# MCU.net
KiCad netlist of a schematic drawn in Altium Designer
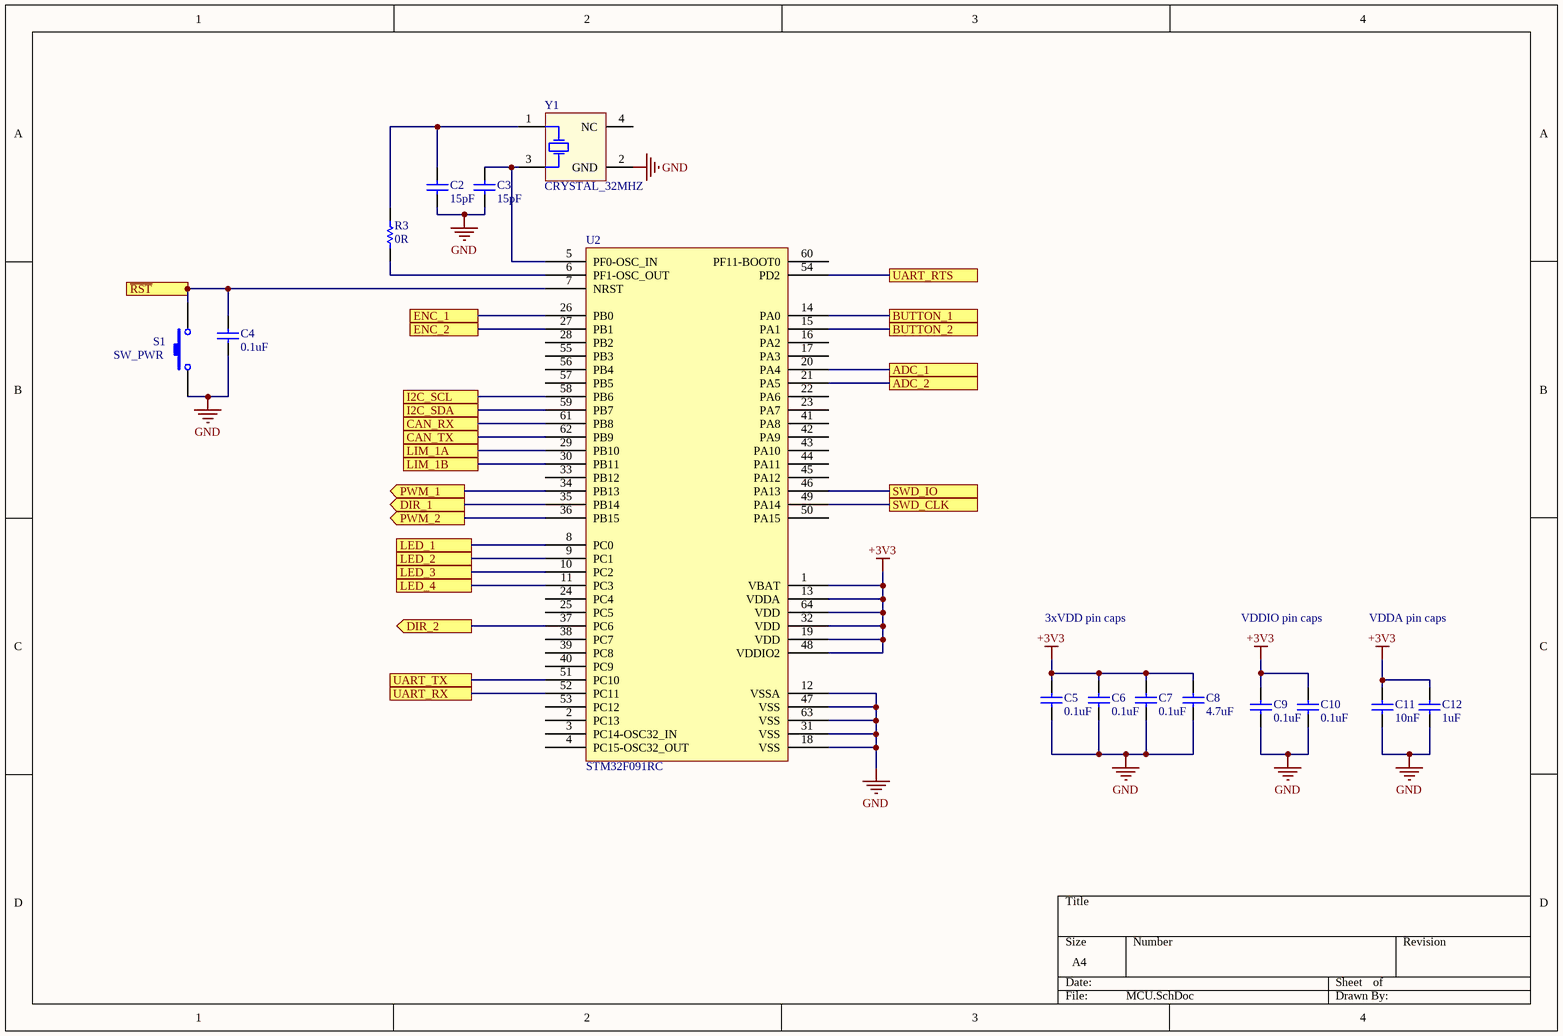
[diagram p0: MCU.SchDoc]

(export (version "E")
  (design (tool "Eeschema 10.0.6"))
  (components
    (comp (ref "C2")
      (value "15pF")
      (footprint "CAPC0603(1608)55_N")
      (description "CAP CER 15PF 250V NPO 0603")
      (fields (field (name "PART NUMBER") "AC0603JRNPOYBN150") (field (name "MANUFACTURER") "Yageo"))
      (libsource (lib "UWRT_Schematic_Library_2019") (part "CAP_15pF_0603"))
    )
    (comp (ref "C3")
      (value "15pF")
      (footprint "CAPC0603(1608)55_N")
      (description "CAP CER 15PF 250V NPO 0603")
      (fields (field (name "PART NUMBER") "AC0603JRNPOYBN150") (field (name "MANUFACTURER") "Yageo"))
      (libsource (lib "UWRT_Schematic_Library_2019") (part "CAP_15pF_0603"))
    )
    (comp (ref "C4")
      (value "0.1uF")
      (footprint "CAPC0603(1608)55_N")
      (description "CAP CER 0.1UF 16V X7R 0603")
      (fields (field (name "PART NUMBER") "CC0603KRX7R7BB104") (field (name "MANUFACTURER") "Yageo"))
      (libsource (lib "UWRT_Schematic_Library_2019") (part "CAP_0.1uF_16V_0603"))
    )
    (comp (ref "C5")
      (value "0.1uF")
      (footprint "CAPC0603(1608)55_N")
      (description "CAP CER 0.1UF 16V X7R 0603")
      (fields (field (name "PART NUMBER") "CC0603KRX7R7BB104") (field (name "MANUFACTURER") "Yageo"))
      (libsource (lib "UWRT_Schematic_Library_2019") (part "CAP_0.1uF_16V_0603"))
    )
    (comp (ref "C6")
      (value "0.1uF")
      (footprint "CAPC0603(1608)55_N")
      (description "CAP CER 0.1UF 16V X7R 0603")
      (fields (field (name "PART NUMBER") "CC0603KRX7R7BB104") (field (name "MANUFACTURER") "Yageo"))
      (libsource (lib "UWRT_Schematic_Library_2019") (part "CAP_0.1uF_16V_0603"))
    )
    (comp (ref "C7")
      (value "0.1uF")
      (footprint "CAPC0603(1608)55_N")
      (description "CAP CER 0.1UF 16V X7R 0603")
      (fields (field (name "PART NUMBER") "CC0603KRX7R7BB104") (field (name "MANUFACTURER") "Yageo"))
      (libsource (lib "UWRT_Schematic_Library_2019") (part "CAP_0.1uF_16V_0603"))
    )
    (comp (ref "C8")
      (value "4.7uF")
      (footprint "CAPC0603(1608)55_N")
      (description "CAP CER 4.7UF 6.3V X5R 0603")
      (fields (field (name "PART NUMBER") "CC0603KRX5R5BB475") (field (name "MANUFACTURER") "Yageo"))
      (libsource (lib "UWRT_Schematic_Library_2019") (part "CAP_4.7uF_0603"))
    )
    (comp (ref "C9")
      (value "0.1uF")
      (footprint "CAPC0603(1608)55_N")
      (description "CAP CER 0.1UF 16V X7R 0603")
      (fields (field (name "PART NUMBER") "CC0603KRX7R7BB104") (field (name "MANUFACTURER") "Yageo"))
      (libsource (lib "UWRT_Schematic_Library_2019") (part "CAP_0.1uF_16V_0603"))
    )
    (comp (ref "C10")
      (value "0.1uF")
      (footprint "CAPC0603(1608)55_N")
      (description "CAP CER 0.1UF 16V X7R 0603")
      (fields (field (name "PART NUMBER") "CC0603KRX7R7BB104") (field (name "MANUFACTURER") "Yageo"))
      (libsource (lib "UWRT_Schematic_Library_2019") (part "CAP_0.1uF_16V_0603"))
    )
    (comp (ref "C11")
      (value "10nF")
      (footprint "CAPC0603(1608)55_N")
      (description "CAP CER 10000PF 16V X7R 0603")
      (fields (field (name "PART NUMBER") "CC0603KRX7R7BB103") (field (name "MANUFACTURER") "Yageo"))
      (libsource (lib "UWRT_Schematic_Library_2019") (part "CAP_10nF_0603"))
    )
    (comp (ref "C12")
      (value "1uF")
      (footprint "CAPC0603(1608)55_N")
      (description "CAP CER 1UF 16V Y5V 0603")
      (fields (field (name "PART NUMBER") "CC0603ZRY5V7BB105") (field (name "MANUFACTURER") "Yageo"))
      (libsource (lib "UWRT_Schematic_Library_2019") (part "CAP_1uF_16V_0603"))
    )
    (comp (ref "R3")
      (value "0R")
      (footprint "RESC0603(1608)_N")
      (description "RES SMD 0 OHM JUMPER 1/10W 0603")
      (fields (field (name "MANUFACTURER") "Yageo") (field (name "Comment") "RES_0R_0603"))
      (libsource (lib "UWRT_Schematic_Library_2019") (part "RES_0R_0603"))
    )
    (comp (ref "S1")
      (value "SW_PWR")
      (footprint "PTS830GM140")
      (description "Power Switch (Red)")
      (fields (field (name "PART NUMBER") "PTS830GM140 SMTR LFS"))
      (libsource (lib "UWRT_Schematic_Library_2019") (part "SW_PWR"))
    )
    (comp (ref "U2")
      (value "STM32F091RC")
      (footprint "UWRT_Footprint_Library_2019:STM_LQFP64_N")
      (fields (field (name "MANUFACTURER") "STMicroelectronics"))
      (libsource (lib "UWRT_Schematic_Library_2019") (part "STM32F091RC"))
    )
    (comp (ref "Y1")
      (value "CRYSTAL_32MHZ")
      (footprint "AVX-CX2520DB32000D0GEJZ1-4_V")
      (description "CRYSTAL 32MHZ 8PF SMD")
      (fields
        (field (name "PART NUMBER") "CX2520DB32000D0GPSC1")
        (field (name "MANUFACTURER") "Kyocera International Inc. Electronic Components")
      )
      (libsource (lib "UWRT_Schematic_Library_2019") (part "CRYSTAL_32MHZ"))
    )
  )
  (nets
    (net (code "1") (name "+3V3") (class "Default")
      (node (ref "C10") (pin "2") (pinfunction "2_2") (pintype "passive"))
      (node (ref "C11") (pin "2") (pinfunction "2_2") (pintype "passive"))
      (node (ref "C12") (pin "2") (pinfunction "2_2") (pintype "passive"))
      (node (ref "C5") (pin "2") (pinfunction "2_2") (pintype "passive"))
      (node (ref "C6") (pin "2") (pinfunction "2_2") (pintype "passive"))
      (node (ref "C7") (pin "2") (pinfunction "2_2") (pintype "passive"))
      (node (ref "C8") (pin "2") (pinfunction "2_2") (pintype "passive"))
      (node (ref "C9") (pin "2") (pinfunction "2_2") (pintype "passive"))
      (node (ref "U2") (pin "1") (pinfunction "VBAT_1") (pintype "passive"))
      (node (ref "U2") (pin "13") (pinfunction "VDDA_13") (pintype "passive"))
      (node (ref "U2") (pin "19") (pinfunction "VDD_19") (pintype "passive"))
      (node (ref "U2") (pin "32") (pinfunction "VDD_32") (pintype "passive"))
      (node (ref "U2") (pin "48") (pinfunction "VDDIO2_48") (pintype "passive"))
      (node (ref "U2") (pin "64") (pinfunction "VDD_64") (pintype "passive"))
    )
    (net (code "2") (name "/ADC_1") (class "Default")
      (node (ref "U2") (pin "20") (pinfunction "PA4_20") (pintype "passive"))
    )
    (net (code "3") (name "/ADC_2") (class "Default")
      (node (ref "U2") (pin "21") (pinfunction "PA5_21") (pintype "passive"))
    )
    (net (code "4") (name "/BUTTON_1") (class "Default")
      (node (ref "U2") (pin "14") (pinfunction "PA0_14") (pintype "passive"))
    )
    (net (code "5") (name "/BUTTON_2") (class "Default")
      (node (ref "U2") (pin "15") (pinfunction "PA1_15") (pintype "passive"))
    )
    (net (code "6") (name "/CAN_RX") (class "Default")
      (node (ref "U2") (pin "61") (pinfunction "PB8_61") (pintype "passive"))
    )
    (net (code "7") (name "/CAN_TX") (class "Default")
      (node (ref "U2") (pin "62") (pinfunction "PB9_62") (pintype "passive"))
    )
    (net (code "8") (name "/DIR_1") (class "Default")
      (node (ref "U2") (pin "35") (pinfunction "PB14_35") (pintype "passive"))
    )
    (net (code "9") (name "/DIR_2") (class "Default")
      (node (ref "U2") (pin "37") (pinfunction "PC6_37") (pintype "passive"))
    )
    (net (code "10") (name "/ENC_1") (class "Default")
      (node (ref "U2") (pin "26") (pinfunction "PB0_26") (pintype "passive"))
    )
    (net (code "11") (name "/ENC_2") (class "Default")
      (node (ref "U2") (pin "27") (pinfunction "PB1_27") (pintype "passive"))
    )
    (net (code "12") (name "/I2C_SCL") (class "Default")
      (node (ref "U2") (pin "58") (pinfunction "PB6_58") (pintype "passive"))
    )
    (net (code "13") (name "/I2C_SDA") (class "Default")
      (node (ref "U2") (pin "59") (pinfunction "PB7_59") (pintype "passive"))
    )
    (net (code "14") (name "/LED_1") (class "Default")
      (node (ref "U2") (pin "8") (pinfunction "PC0_8") (pintype "passive"))
    )
    (net (code "15") (name "/LED_2") (class "Default")
      (node (ref "U2") (pin "9") (pinfunction "PC1_9") (pintype "passive"))
    )
    (net (code "16") (name "/LED_3") (class "Default")
      (node (ref "U2") (pin "10") (pinfunction "PC2_10") (pintype "passive"))
    )
    (net (code "17") (name "/LED_4") (class "Default")
      (node (ref "U2") (pin "11") (pinfunction "PC3_11") (pintype "passive"))
    )
    (net (code "18") (name "/LIM_1A") (class "Default")
      (node (ref "U2") (pin "29") (pinfunction "PB10_29") (pintype "passive"))
    )
    (net (code "19") (name "/LIM_1B") (class "Default")
      (node (ref "U2") (pin "30") (pinfunction "PB11_30") (pintype "passive"))
    )
    (net (code "20") (name "/PWM_1") (class "Default")
      (node (ref "U2") (pin "34") (pinfunction "PB13_34") (pintype "passive"))
    )
    (net (code "21") (name "/PWM_2") (class "Default")
      (node (ref "U2") (pin "36") (pinfunction "PB15_36") (pintype "passive"))
    )
    (net (code "22") (name "/SWD_CLK") (class "Default")
      (node (ref "U2") (pin "49") (pinfunction "PA14_49") (pintype "passive"))
    )
    (net (code "23") (name "/SWD_IO") (class "Default")
      (node (ref "U2") (pin "46") (pinfunction "PA13_46") (pintype "passive"))
    )
    (net (code "24") (name "/UART_RTS") (class "Default")
      (node (ref "U2") (pin "54") (pinfunction "PD2_54") (pintype "passive"))
    )
    (net (code "25") (name "/UART_RX") (class "Default")
      (node (ref "U2") (pin "52") (pinfunction "PC11_52") (pintype "passive"))
    )
    (net (code "26") (name "/UART_TX") (class "Default")
      (node (ref "U2") (pin "51") (pinfunction "PC10_51") (pintype "passive"))
    )
    (net (code "27") (name "/~{RST}") (class "Default")
      (node (ref "C4") (pin "2") (pinfunction "2_2") (pintype "passive"))
      (node (ref "S1") (pin "2") (pinfunction "2_2") (pintype "passive"))
      (node (ref "U2") (pin "7") (pinfunction "NRST_7") (pintype "passive"))
    )
    (net (code "28") (name "GND") (class "Default")
      (node (ref "C10") (pin "1") (pinfunction "1_1") (pintype "passive"))
      (node (ref "C11") (pin "1") (pinfunction "1_1") (pintype "passive"))
      (node (ref "C12") (pin "1") (pinfunction "1_1") (pintype "passive"))
      (node (ref "C2") (pin "1") (pinfunction "1_1") (pintype "passive"))
      (node (ref "C3") (pin "1") (pinfunction "1_1") (pintype "passive"))
      (node (ref "C4") (pin "1") (pinfunction "1_1") (pintype "passive"))
      (node (ref "C5") (pin "1") (pinfunction "1_1") (pintype "passive"))
      (node (ref "C6") (pin "1") (pinfunction "1_1") (pintype "passive"))
      (node (ref "C7") (pin "1") (pinfunction "1_1") (pintype "passive"))
      (node (ref "C8") (pin "1") (pinfunction "1_1") (pintype "passive"))
      (node (ref "C9") (pin "1") (pinfunction "1_1") (pintype "passive"))
      (node (ref "S1") (pin "1") (pinfunction "1_1") (pintype "passive"))
      (node (ref "U2") (pin "12") (pinfunction "VSSA_12") (pintype "passive"))
      (node (ref "U2") (pin "18") (pinfunction "VSS_18") (pintype "passive"))
      (node (ref "U2") (pin "31") (pinfunction "VSS_31") (pintype "passive"))
      (node (ref "U2") (pin "47") (pinfunction "VSS_47") (pintype "passive"))
      (node (ref "U2") (pin "63") (pinfunction "VSS_63") (pintype "passive"))
      (node (ref "Y1") (pin "2") (pinfunction "GND_2") (pintype "power_in"))
    )
    (net (code "29") (name "Net-(C2-Pad2)") (class "Default")
      (node (ref "C2") (pin "2") (pinfunction "2_2") (pintype "passive"))
      (node (ref "R3") (pin "2") (pinfunction "2_2") (pintype "passive"))
      (node (ref "Y1") (pin "1") (pinfunction "HOT_1") (pintype "passive"))
    )
    (net (code "30") (name "Net-(U2-PF0-OSC_IN)") (class "Default")
      (node (ref "C3") (pin "2") (pinfunction "2_2") (pintype "passive"))
      (node (ref "U2") (pin "5") (pinfunction "PF0-OSC_IN_5") (pintype "passive"))
      (node (ref "Y1") (pin "3") (pinfunction "HOT_3") (pintype "passive"))
    )
    (net (code "31") (name "Net-(U2-PF1-OSC_OUT)") (class "Default")
      (node (ref "R3") (pin "1") (pinfunction "1_1") (pintype "passive"))
      (node (ref "U2") (pin "6") (pinfunction "PF1-OSC_OUT_6") (pintype "passive"))
    )
    (net (code "32") (name "unconnected-(U2-PA2-Pad16)") (class "Default")
      (node (ref "U2") (pin "16") (pinfunction "PA2_16") (pintype "passive"))
    )
    (net (code "33") (name "unconnected-(U2-PA3-Pad17)") (class "Default")
      (node (ref "U2") (pin "17") (pinfunction "PA3_17") (pintype "passive"))
    )
    (net (code "34") (name "unconnected-(U2-PA6-Pad22)") (class "Default")
      (node (ref "U2") (pin "22") (pinfunction "PA6_22") (pintype "passive"))
    )
    (net (code "35") (name "unconnected-(U2-PA7-Pad23)") (class "Default")
      (node (ref "U2") (pin "23") (pinfunction "PA7_23") (pintype "passive"))
    )
    (net (code "36") (name "unconnected-(U2-PA8-Pad41)") (class "Default")
      (node (ref "U2") (pin "41") (pinfunction "PA8_41") (pintype "passive"))
    )
    (net (code "37") (name "unconnected-(U2-PA9-Pad42)") (class "Default")
      (node (ref "U2") (pin "42") (pinfunction "PA9_42") (pintype "passive"))
    )
    (net (code "38") (name "unconnected-(U2-PA10-Pad43)") (class "Default")
      (node (ref "U2") (pin "43") (pinfunction "PA10_43") (pintype "passive"))
    )
    (net (code "39") (name "unconnected-(U2-PA11-Pad44)") (class "Default")
      (node (ref "U2") (pin "44") (pinfunction "PA11_44") (pintype "passive"))
    )
    (net (code "40") (name "unconnected-(U2-PA12-Pad45)") (class "Default")
      (node (ref "U2") (pin "45") (pinfunction "PA12_45") (pintype "passive"))
    )
    (net (code "41") (name "unconnected-(U2-PA15-Pad50)") (class "Default")
      (node (ref "U2") (pin "50") (pinfunction "PA15_50") (pintype "passive"))
    )
    (net (code "42") (name "unconnected-(U2-PB2-Pad28)") (class "Default")
      (node (ref "U2") (pin "28") (pinfunction "PB2_28") (pintype "passive"))
    )
    (net (code "43") (name "unconnected-(U2-PB3-Pad55)") (class "Default")
      (node (ref "U2") (pin "55") (pinfunction "PB3_55") (pintype "passive"))
    )
    (net (code "44") (name "unconnected-(U2-PB4-Pad56)") (class "Default")
      (node (ref "U2") (pin "56") (pinfunction "PB4_56") (pintype "passive"))
    )
    (net (code "45") (name "unconnected-(U2-PB5-Pad57)") (class "Default")
      (node (ref "U2") (pin "57") (pinfunction "PB5_57") (pintype "passive"))
    )
    (net (code "46") (name "unconnected-(U2-PB12-Pad33)") (class "Default")
      (node (ref "U2") (pin "33") (pinfunction "PB12_33") (pintype "passive"))
    )
    (net (code "47") (name "unconnected-(U2-PC4-Pad24)") (class "Default")
      (node (ref "U2") (pin "24") (pinfunction "PC4_24") (pintype "passive"))
    )
    (net (code "48") (name "unconnected-(U2-PC5-Pad25)") (class "Default")
      (node (ref "U2") (pin "25") (pinfunction "PC5_25") (pintype "passive"))
    )
    (net (code "49") (name "unconnected-(U2-PC7-Pad38)") (class "Default")
      (node (ref "U2") (pin "38") (pinfunction "PC7_38") (pintype "passive"))
    )
    (net (code "50") (name "unconnected-(U2-PC8-Pad39)") (class "Default")
      (node (ref "U2") (pin "39") (pinfunction "PC8_39") (pintype "passive"))
    )
    (net (code "51") (name "unconnected-(U2-PC9-Pad40)") (class "Default")
      (node (ref "U2") (pin "40") (pinfunction "PC9_40") (pintype "passive"))
    )
    (net (code "52") (name "unconnected-(U2-PC12-Pad53)") (class "Default")
      (node (ref "U2") (pin "53") (pinfunction "PC12_53") (pintype "passive"))
    )
    (net (code "53") (name "unconnected-(U2-PC13-Pad2)") (class "Default")
      (node (ref "U2") (pin "2") (pinfunction "PC13_2") (pintype "passive"))
    )
    (net (code "54") (name "unconnected-(U2-PC14-OSC32_IN-Pad3)") (class "Default")
      (node (ref "U2") (pin "3") (pinfunction "PC14-OSC32_IN_3") (pintype "passive"))
    )
    (net (code "55") (name "unconnected-(U2-PC15-OSC32_OUT-Pad4)") (class "Default")
      (node (ref "U2") (pin "4") (pinfunction "PC15-OSC32_OUT_4") (pintype "passive"))
    )
    (net (code "56") (name "unconnected-(U2-PF11-BOOT0-Pad60)") (class "Default")
      (node (ref "U2") (pin "60") (pinfunction "PF11-BOOT0_60") (pintype "passive"))
    )
    (net (code "57") (name "unconnected-(Y1-NC-Pad4)") (class "Default")
      (node (ref "Y1") (pin "4") (pinfunction "NC_4") (pintype "passive"))
    )
  )
)
